# power.net
KiCad netlist of a schematic drawn in Altium Designer
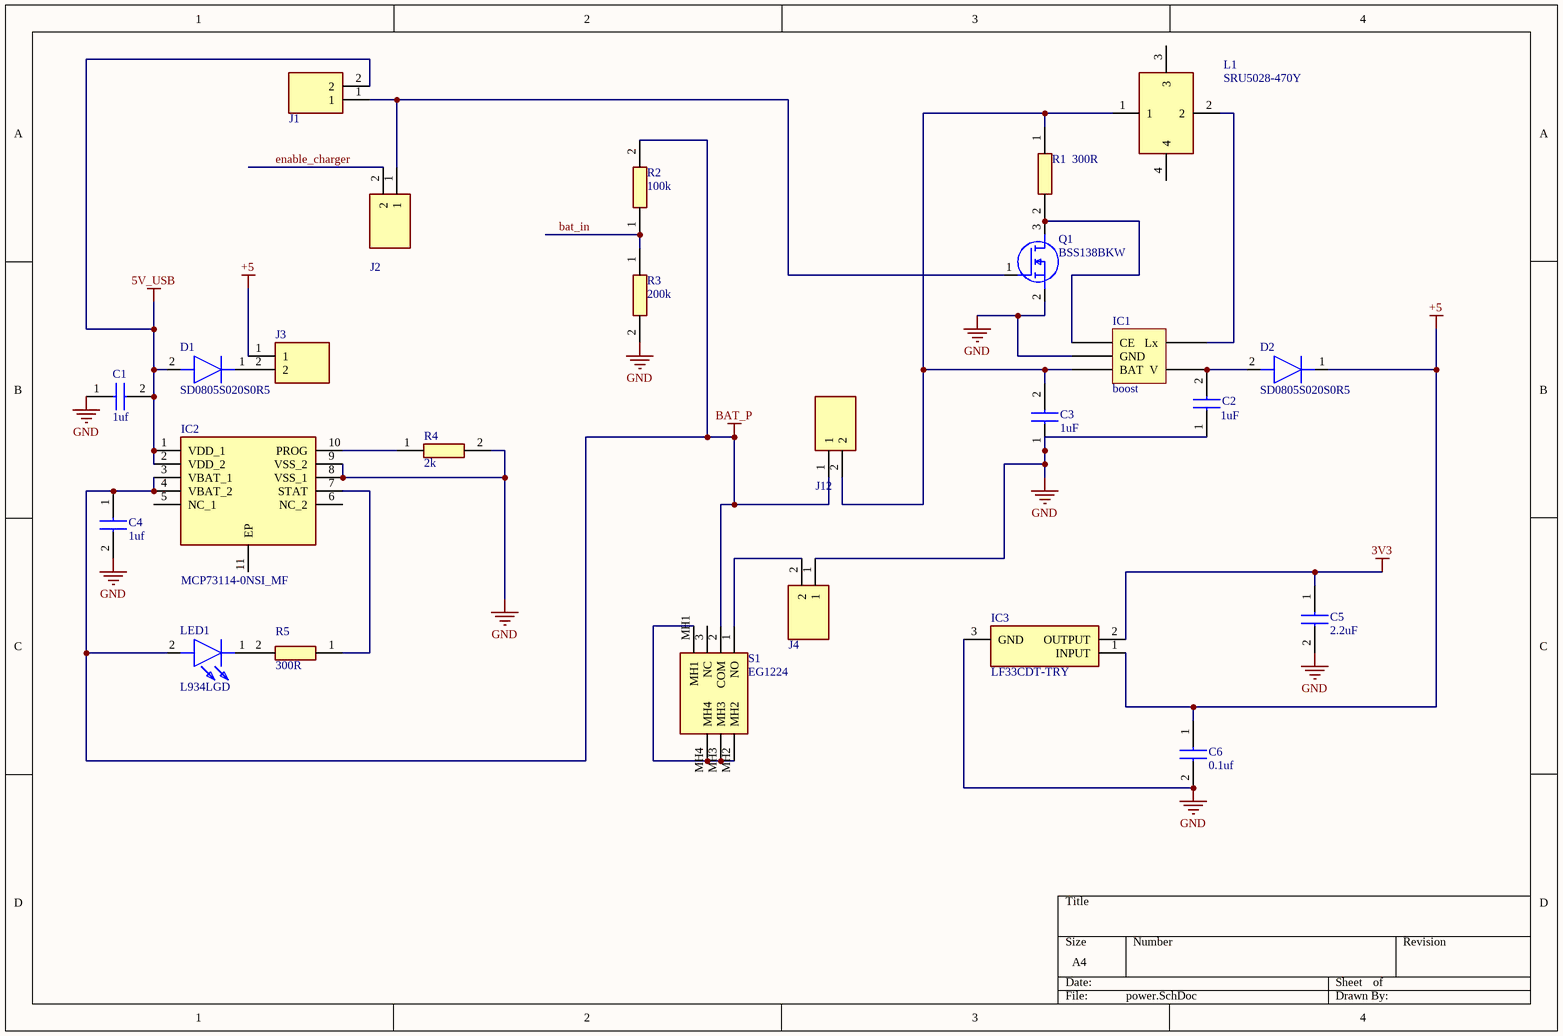
[diagram p0: power.SchDoc]

(export (version "E")
  (design (tool "Eeschema 10.0.6"))
  (components
    (comp (ref "C1")
      (value "1uf")
      (footprint "SamacSys:C0805")
      (description "Capacitor")
      (fields (field (name "MANUFACTURER_PART_NUMBER") "C0805C104J5RACTM"))
      (libsource (lib "*") (part "C0805C104J5RACTM"))
    )
    (comp (ref "C2")
      (value "1uF")
      (footprint "SamacSys:CAPC2114X145N")
      (description "Capacitor")
      (fields
        (field (name "MANUFACTURER_PART_NUMBER") "LMR212BD7106KG-T")
        (field (name "MOUSER PART NUMBER") "963-LMR212BD7106KG-T")
      )
      (libsource (lib "*") (part "LMR212BD7106KG-T"))
    )
    (comp (ref "C3")
      (value "1uF")
      (footprint "SamacSys:CAPC2114X145N")
      (description "Capacitor")
      (fields
        (field (name "MANUFACTURER_PART_NUMBER") "LMR212BD7106KG-T")
        (field (name "MOUSER PART NUMBER") "963-LMR212BD7106KG-T")
      )
      (libsource (lib "*") (part "LMR212BD7106KG-T"))
    )
    (comp (ref "C4")
      (value "1uf")
      (footprint "SamacSys:C0805")
      (description "Capacitor")
      (fields (field (name "MANUFACTURER_PART_NUMBER") "C0805C104J5RACTM"))
      (libsource (lib "*") (part "C0805C104J5RACTM"))
    )
    (comp (ref "C5")
      (value "2.2uF")
      (footprint "SamacSys:CAPC2012X152N")
      (description "Capacitor")
      (fields
        (field (name "MANUFACTURER_PART_NUMBER") "08055C225KAT2A")
        (field (name "MOUSER PART NUMBER") "581-08055C225KAT2A")
      )
      (libsource (lib "*") (part "08055C225KAT2A"))
    )
    (comp (ref "C6")
      (value "0.1uf")
      (footprint "SamacSys:C0805")
      (description "Capacitor")
      (fields (field (name "MANUFACTURER_PART_NUMBER") "C0805C104J5RACTM"))
      (libsource (lib "*") (part "C0805C104J5RACTM"))
    )
    (comp (ref "D1")
      (value "SD0805S020S0R5")
      (footprint "SamacSys:DIOC2013X100N")
      (description "Diode")
      (fields (field (name "MOUSER PART NUMBER") "581-SD0805S020S0R5"))
      (libsource (lib "*") (part "SD0805S020S0R5"))
    )
    (comp (ref "D2")
      (value "SD0805S020S0R5")
      (footprint "SamacSys:DIOC2013X100N")
      (description "Diode")
      (fields (field (name "MOUSER PART NUMBER") "581-SD0805S020S0R5"))
      (libsource (lib "*") (part "SD0805S020S0R5"))
    )
    (comp (ref "IC1")
      (value "boost")
      (footprint "SOT95P280X110-5N")
      (libsource (lib "vuserial") (part "boost"))
    )
    (comp (ref "IC2")
      (value "MCP73114-0NSI_MF")
      (footprint "SamacSys:SON50P300X300X100-11N-D")
      (description "Integrated Circuit")
      (fields
        (field (name "MANUFACTURER_PART_NUMBER") "MCP73114-0NSI/MF")
        (field (name "MOUSER PART NUMBER") "579-MCP73114-0NSI/MF")
      )
      (libsource (lib "*") (part "MCP73114-0NSI_MF"))
    )
    (comp (ref "IC3")
      (value "LF33CDT-TRY")
      (footprint "SamacSys:LD1117DT33")
      (description "Integrated Circuit")
      (fields (field (name "MOUSER PART NUMBER") "511-LF33CDT-TRY"))
      (libsource (lib "*") (part "LF33CDT-TRY"))
    )
    (comp (ref "J1")
      (value "10129378-902001BLF")
      (footprint "SamacSys:HDRV2W67P0X254_1X2_508X241X843P")
      (description "Connector")
      (fields (field (name "MOUSER PART NUMBER") "649-1012937890201BLF"))
      (libsource (lib "") (part "10129378-902001BLF_3"))
    )
    (comp (ref "J2")
      (value "10129378-902001BLF")
      (footprint "SamacSys:HDRV2W67P0X254_1X2_508X241X843P")
      (description "Connector")
      (fields (field (name "MOUSER PART NUMBER") "649-1012937890201BLF"))
      (libsource (lib "*") (part "10129378-902001BLF"))
    )
    (comp (ref "J3")
      (value "10129378-902001BLF")
      (footprint "SamacSys:HDRV2W67P0X254_1X2_508X241X843P")
      (description "Connector")
      (fields (field (name "MOUSER PART NUMBER") "649-1012937890201BLF"))
      (libsource (lib "") (part "10129378-902001BLF_1"))
    )
    (comp (ref "J4")
      (value "10129378-902001BLF")
      (footprint "SamacSys:HDRV2W67P0X254_1X2_508X241X843P")
      (description "Connector")
      (fields (field (name "MOUSER PART NUMBER") "649-1012937890201BLF"))
      (libsource (lib "*") (part "10129378-902001BLF"))
    )
    (comp (ref "J12")
      (value "10129378-902001BLF")
      (footprint "SamacSys:HDRV2W67P0X254_1X2_508X241X843P")
      (description "Connector")
      (fields (field (name "MOUSER PART NUMBER") "649-1012937890201BLF"))
      (libsource (lib "") (part "10129378-902001BLF_2"))
    )
    (comp (ref "L1")
      (value "SRU5028-470Y")
      (footprint "SamacSys:SRU5028")
      (description "Inductor")
      (fields (field (name "MOUSER PART NUMBER") "652-SRU5028-470Y"))
      (libsource (lib "*") (part "SRU5028-470Y"))
    )
    (comp (ref "LED1")
      (value "L934LGD")
      (footprint "SamacSys:L934LGD")
      (description "LED")
      (fields (field (name "MOUSER PART NUMBER") "604-L934LGD"))
      (libsource (lib "*") (part "L934LGD"))
    )
    (comp (ref "Q1")
      (value "BSS138BKW")
      (footprint "SamacSys:SOT65P210X110-3N")
      (description "MOSFET (N-Channel)")
      (libsource (lib "*") (part "BSS138BKW"))
    )
    (comp (ref "R1")
      (value "300R")
      (footprint "SamacSys:RESC2012X65N")
      (description "Resistor")
      (fields
        (field (name "MANUFACTURER_PART_NUMBER") "CPF0805B300RE1")
        (field (name "MOUSER PART NUMBER") "279-CPF0805B300RE1")
      )
      (libsource (lib "*") (part "CPF0805B300RE1"))
    )
    (comp (ref "R2")
      (value "100k")
      (footprint "SamacSys:RESC2012X60N")
      (description "Resistor")
      (fields
        (field (name "MANUFACTURER_PART_NUMBER") "CRCW0805100KFKEAHP")
        (field (name "MOUSER PART NUMBER") "71-CRCW0805100KFKEAH")
      )
      (libsource (lib "*") (part "CRCW0805100KFKEAHP"))
    )
    (comp (ref "R3")
      (value "200k")
      (footprint "SamacSys:RESC2012X65N")
      (description "Resistor")
      (fields (field (name "MANUFACTURER_PART_NUMBER") "CPF0805B200KE"))
      (libsource (lib "*") (part "CPF0805B200KE"))
    )
    (comp (ref "R4")
      (value "2k")
      (footprint "SamacSys:RESC2012X65N")
      (description "Resistor")
      (fields (field (name "MANUFACTURER_PART_NUMBER") "CPF0805B2K1E"))
      (libsource (lib "*") (part "CPF0805B2K1E"))
    )
    (comp (ref "R5")
      (value "300R")
      (footprint "SamacSys:RESC2012X65N")
      (description "Resistor")
      (fields
        (field (name "MANUFACTURER_PART_NUMBER") "CPF0805B300RE1")
        (field (name "MOUSER PART NUMBER") "279-CPF0805B300RE1")
      )
      (libsource (lib "") (part "CPF0805B300RE1_1"))
    )
    (comp (ref "S1")
      (value "EG1224")
      (footprint "SamacSys:EG1224")
      (description "Switch")
      (fields (field (name "MOUSER PART NUMBER") "612-EG1224"))
      (libsource (lib "*") (part "EG1224"))
    )
  )
  (nets
    (net (code "1") (name "+5") (class "Default")
      (node (ref "C6") (pin "1") (pinfunction "1_1") (pintype "passive"))
      (node (ref "D2") (pin "1") (pinfunction "K_1") (pintype "passive"))
      (node (ref "IC3") (pin "1") (pinfunction "INPUT_1") (pintype "passive"))
      (node (ref "J3") (pin "1") (pinfunction "1_1") (pintype "passive"))
    )
    (net (code "2") (name "/bat_in") (class "Default")
      (node (ref "R2") (pin "1") (pinfunction "1_1") (pintype "passive"))
      (node (ref "R3") (pin "1") (pinfunction "1_1") (pintype "passive"))
    )
    (net (code "3") (name "/enable_charger") (class "Default")
      (node (ref "J2") (pin "2") (pinfunction "2_2") (pintype "passive"))
    )
    (net (code "4") (name "3V3") (class "Default")
      (node (ref "C5") (pin "1") (pinfunction "1_1") (pintype "passive"))
      (node (ref "IC3") (pin "2") (pinfunction "OUTPUT_2") (pintype "passive"))
    )
    (net (code "5") (name "5V_USB") (class "Default")
      (node (ref "C1") (pin "2") (pinfunction "2_2") (pintype "passive"))
      (node (ref "D1") (pin "2") (pinfunction "A_2") (pintype "passive"))
      (node (ref "IC2") (pin "1") (pinfunction "VDD_1_1") (pintype "passive"))
      (node (ref "IC2") (pin "2") (pinfunction "VDD_2_2") (pintype "passive"))
      (node (ref "J1") (pin "2") (pinfunction "2_2") (pintype "passive"))
    )
    (net (code "6") (name "BAT_P") (class "Default")
      (node (ref "C4") (pin "1") (pinfunction "1_1") (pintype "passive"))
      (node (ref "IC2") (pin "3") (pinfunction "VBAT_1_3") (pintype "passive"))
      (node (ref "IC2") (pin "4") (pinfunction "VBAT_2_4") (pintype "passive"))
      (node (ref "J12") (pin "1") (pinfunction "1_1") (pintype "passive"))
      (node (ref "LED1") (pin "2") (pinfunction "A_2") (pintype "passive"))
      (node (ref "R2") (pin "2") (pinfunction "2_2") (pintype "passive"))
      (node (ref "S1") (pin "2") (pinfunction "COM_2") (pintype "passive"))
    )
    (net (code "7") (name "GND") (class "Default")
      (node (ref "C1") (pin "1") (pinfunction "1_1") (pintype "passive"))
      (node (ref "C2") (pin "1") (pinfunction "1_1") (pintype "passive"))
      (node (ref "C3") (pin "1") (pinfunction "1_1") (pintype "passive"))
      (node (ref "C4") (pin "2") (pinfunction "2_2") (pintype "passive"))
      (node (ref "C5") (pin "2") (pinfunction "2_2") (pintype "passive"))
      (node (ref "C6") (pin "2") (pinfunction "2_2") (pintype "passive"))
      (node (ref "IC1") (pin "2") (pinfunction "GND_2") (pintype "passive"))
      (node (ref "IC2") (pin "8") (pinfunction "VSS_1_8") (pintype "passive"))
      (node (ref "IC2") (pin "9") (pinfunction "VSS_2_9") (pintype "passive"))
      (node (ref "IC3") (pin "3") (pinfunction "GND_3") (pintype "passive"))
      (node (ref "J4") (pin "1") (pinfunction "1_1") (pintype "passive"))
      (node (ref "Q1") (pin "2") (pinfunction "S_2") (pintype "passive"))
      (node (ref "R3") (pin "2") (pinfunction "2_2") (pintype "passive"))
      (node (ref "R4") (pin "2") (pinfunction "2_2") (pintype "passive"))
    )
    (net (code "8") (name "Net-(D1-K)") (class "Default")
      (node (ref "D1") (pin "1") (pinfunction "K_1") (pintype "passive"))
      (node (ref "J3") (pin "2") (pinfunction "2_2") (pintype "passive"))
    )
    (net (code "9") (name "Net-(D2-A)") (class "Default")
      (node (ref "C2") (pin "2") (pinfunction "2_2") (pintype "passive"))
      (node (ref "D2") (pin "2") (pinfunction "A_2") (pintype "passive"))
      (node (ref "IC1") (pin "4") (pinfunction "V_4") (pintype "passive"))
    )
    (net (code "10") (name "Net-(IC1-BAT)") (class "Default")
      (node (ref "C3") (pin "2") (pinfunction "2_2") (pintype "passive"))
      (node (ref "IC1") (pin "3") (pinfunction "BAT_3") (pintype "passive"))
      (node (ref "J12") (pin "2") (pinfunction "2_2") (pintype "passive"))
      (node (ref "L1") (pin "1") (pinfunction "1_1") (pintype "passive"))
      (node (ref "R1") (pin "1") (pinfunction "1_1") (pintype "passive"))
    )
    (net (code "11") (name "Net-(IC1-CE)") (class "Default")
      (node (ref "IC1") (pin "1") (pinfunction "CE_1") (pintype "passive"))
      (node (ref "Q1") (pin "3") (pinfunction "D_3") (pintype "passive"))
      (node (ref "R1") (pin "2") (pinfunction "2_2") (pintype "passive"))
    )
    (net (code "12") (name "Net-(IC1-Lx)") (class "Default")
      (node (ref "IC1") (pin "5") (pinfunction "Lx_5") (pintype "passive"))
      (node (ref "L1") (pin "2") (pinfunction "2_2") (pintype "passive"))
    )
    (net (code "13") (name "Net-(IC2-PROG)") (class "Default")
      (node (ref "IC2") (pin "10") (pinfunction "PROG_10") (pintype "passive"))
      (node (ref "R4") (pin "1") (pinfunction "1_1") (pintype "passive"))
    )
    (net (code "14") (name "Net-(IC2-STAT)") (class "Default")
      (node (ref "IC2") (pin "7") (pinfunction "STAT_7") (pintype "passive"))
      (node (ref "R5") (pin "1") (pinfunction "1_1") (pintype "passive"))
    )
    (net (code "15") (name "Net-(LED1-K)") (class "Default")
      (node (ref "LED1") (pin "1") (pinfunction "K_1") (pintype "passive"))
      (node (ref "R5") (pin "2") (pinfunction "2_2") (pintype "passive"))
    )
    (net (code "16") (name "Net-(Q1-G)") (class "Default")
      (node (ref "J1") (pin "1") (pinfunction "1_1") (pintype "passive"))
      (node (ref "J2") (pin "1") (pinfunction "1_1") (pintype "passive"))
      (node (ref "Q1") (pin "1") (pinfunction "G_1") (pintype "passive"))
    )
    (net (code "17") (name "Net-(S1-NO)") (class "Default")
      (node (ref "J4") (pin "2") (pinfunction "2_2") (pintype "passive"))
      (node (ref "S1") (pin "1") (pinfunction "NO_1") (pintype "passive"))
    )
    (net (code "18") (name "Net-(S1-PadMH1)") (class "Default")
      (node (ref "S1") (pin "MH1") (pinfunction "MH1_MH1") (pintype "passive"))
      (node (ref "S1") (pin "MH2") (pinfunction "MH2_MH2") (pintype "passive"))
      (node (ref "S1") (pin "MH3") (pinfunction "MH3_MH3") (pintype "passive"))
      (node (ref "S1") (pin "MH4") (pinfunction "MH4_MH4") (pintype "passive"))
    )
    (net (code "19") (name "unconnected-(IC2-EP-Pad11)") (class "Default")
      (node (ref "IC2") (pin "11") (pinfunction "EP_11") (pintype "passive"))
    )
    (net (code "20") (name "unconnected-(IC2-NC_1-Pad5)") (class "Default")
      (node (ref "IC2") (pin "5") (pinfunction "NC_1_5") (pintype "passive"))
    )
    (net (code "21") (name "unconnected-(IC2-NC_2-Pad6)") (class "Default")
      (node (ref "IC2") (pin "6") (pinfunction "NC_2_6") (pintype "passive"))
    )
    (net (code "22") (name "unconnected-(L1-Pad3)") (class "Default")
      (node (ref "L1") (pin "3") (pinfunction "3_3") (pintype "passive"))
    )
    (net (code "23") (name "unconnected-(L1-Pad4)") (class "Default")
      (node (ref "L1") (pin "4") (pinfunction "4_4") (pintype "passive"))
    )
    (net (code "24") (name "unconnected-(S1-NC-Pad3)") (class "Default")
      (node (ref "S1") (pin "3") (pinfunction "NC_3") (pintype "passive"))
    )
  )
)
